# LineSensors.net
KiCad netlist of a schematic drawn in Altium Designer
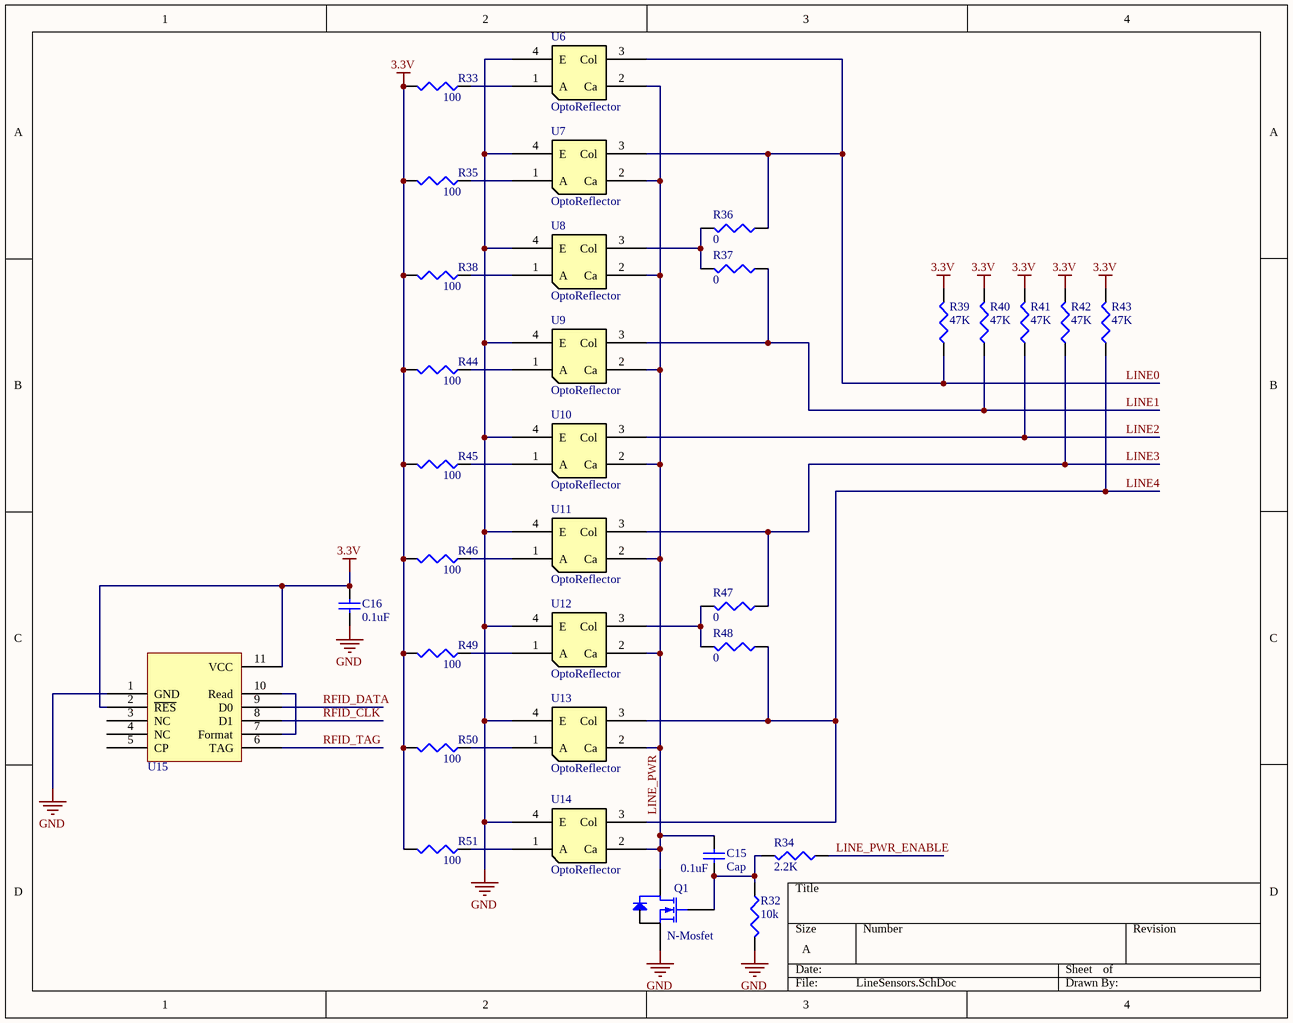
[diagram p0: LineSensors.SchDoc]

(export (version "E")
  (design (tool "Eeschema 10.0.6"))
  (components
    (comp (ref "C15")
      (value "Cap")
      (footprint "CAPC1005L")
      (description "Capacitor")
      (fields (field (name "ALTIUM_VALUE") "0.1uF") (field (name "PUBLISHER") "Altium Limited"))
      (libsource (lib "mrone") (part "Cap"))
    )
    (comp (ref "C16")
      (value "0.1uF")
      (footprint "CAPC1005L")
      (description "Capacitor (Semiconductor SIM Model)")
      (fields (field (name "Comment") "Cap Semi") (field (name "PUBLISHER") "Altium Limited"))
      (libsource (lib "Miscellaneous Devices") (part "Cap Semi"))
    )
    (comp (ref "Q1") (value "N-Mosfet") (footprint "SOT-23") (libsource (lib "mrone") (part "N-Mosfet")))
    (comp (ref "R32")
      (value "10k")
      (footprint "J1-0603")
      (description "Resistor")
      (fields (field (name "Comment") "Res3") (field (name "PUBLISHER") "Altium Limited"))
      (libsource (lib "Miscellaneous Devices") (part "Res3"))
    )
    (comp (ref "R33")
      (value "100")
      (footprint "J1-0603")
      (description "Resistor")
      (fields (field (name "Comment") "Res3") (field (name "PUBLISHER") "Altium Limited"))
      (libsource (lib "Miscellaneous Devices") (part "Res3"))
    )
    (comp (ref "R34")
      (value "2.2K")
      (footprint "J1-0603")
      (description "Resistor")
      (fields (field (name "Comment") "Res3") (field (name "PUBLISHER") "Altium Limited"))
      (libsource (lib "Miscellaneous Devices") (part "Res3"))
    )
    (comp (ref "R35")
      (value "100")
      (footprint "J1-0603")
      (description "Resistor")
      (fields (field (name "Comment") "Res3") (field (name "PUBLISHER") "Altium Limited"))
      (libsource (lib "Miscellaneous Devices") (part "Res3"))
    )
    (comp (ref "R36")
      (value "0")
      (footprint "J1-0603")
      (description "Resistor")
      (fields (field (name "Comment") "Res3") (field (name "PUBLISHER") "Altium Limited"))
      (libsource (lib "Miscellaneous Devices") (part "Res3"))
    )
    (comp (ref "R37")
      (value "0")
      (footprint "J1-0603")
      (description "Resistor")
      (fields (field (name "Comment") "Res3") (field (name "PUBLISHER") "Altium Limited"))
      (libsource (lib "Miscellaneous Devices") (part "Res3"))
    )
    (comp (ref "R38")
      (value "100")
      (footprint "J1-0603")
      (description "Resistor")
      (fields (field (name "Comment") "Res3") (field (name "PUBLISHER") "Altium Limited"))
      (libsource (lib "Miscellaneous Devices") (part "Res3"))
    )
    (comp (ref "R39")
      (value "47K")
      (footprint "J1-0603")
      (description "Resistor")
      (fields (field (name "Comment") "Res3") (field (name "PUBLISHER") "Altium Limited"))
      (libsource (lib "Miscellaneous Devices") (part "Res3"))
    )
    (comp (ref "R40")
      (value "47K")
      (footprint "J1-0603")
      (description "Resistor")
      (fields (field (name "Comment") "Res3") (field (name "PUBLISHER") "Altium Limited"))
      (libsource (lib "Miscellaneous Devices") (part "Res3"))
    )
    (comp (ref "R41")
      (value "47K")
      (footprint "J1-0603")
      (description "Resistor")
      (fields (field (name "Comment") "Res3") (field (name "PUBLISHER") "Altium Limited"))
      (libsource (lib "Miscellaneous Devices") (part "Res3"))
    )
    (comp (ref "R42")
      (value "47K")
      (footprint "J1-0603")
      (description "Resistor")
      (fields (field (name "Comment") "Res3") (field (name "PUBLISHER") "Altium Limited"))
      (libsource (lib "Miscellaneous Devices") (part "Res3"))
    )
    (comp (ref "R43")
      (value "47K")
      (footprint "J1-0603")
      (description "Resistor")
      (fields (field (name "Comment") "Res3") (field (name "PUBLISHER") "Altium Limited"))
      (libsource (lib "Miscellaneous Devices") (part "Res3"))
    )
    (comp (ref "R44")
      (value "100")
      (footprint "J1-0603")
      (description "Resistor")
      (fields (field (name "Comment") "Res3") (field (name "PUBLISHER") "Altium Limited"))
      (libsource (lib "Miscellaneous Devices") (part "Res3"))
    )
    (comp (ref "R45")
      (value "100")
      (footprint "J1-0603")
      (description "Resistor")
      (fields (field (name "Comment") "Res3") (field (name "PUBLISHER") "Altium Limited"))
      (libsource (lib "Miscellaneous Devices") (part "Res3"))
    )
    (comp (ref "R46")
      (value "100")
      (footprint "J1-0603")
      (description "Resistor")
      (fields (field (name "Comment") "Res3") (field (name "PUBLISHER") "Altium Limited"))
      (libsource (lib "Miscellaneous Devices") (part "Res3"))
    )
    (comp (ref "R47")
      (value "0")
      (footprint "J1-0603")
      (description "Resistor")
      (fields (field (name "Comment") "Res3") (field (name "PUBLISHER") "Altium Limited"))
      (libsource (lib "Miscellaneous Devices") (part "Res3"))
    )
    (comp (ref "R48")
      (value "0")
      (footprint "J1-0603")
      (description "Resistor")
      (fields (field (name "Comment") "Res3") (field (name "PUBLISHER") "Altium Limited"))
      (libsource (lib "Miscellaneous Devices") (part "Res3"))
    )
    (comp (ref "R49")
      (value "100")
      (footprint "J1-0603")
      (description "Resistor")
      (fields (field (name "Comment") "Res3") (field (name "PUBLISHER") "Altium Limited"))
      (libsource (lib "Miscellaneous Devices") (part "Res3"))
    )
    (comp (ref "R50")
      (value "100")
      (footprint "J1-0603")
      (description "Resistor")
      (fields (field (name "Comment") "Res3") (field (name "PUBLISHER") "Altium Limited"))
      (libsource (lib "Miscellaneous Devices") (part "Res3"))
    )
    (comp (ref "R51")
      (value "100")
      (footprint "J1-0603")
      (description "Resistor")
      (fields (field (name "Comment") "Res3") (field (name "PUBLISHER") "Altium Limited"))
      (libsource (lib "Miscellaneous Devices") (part "Res3"))
    )
    (comp (ref "U6")
      (value "OptoReflector")
      (footprint "QRE1113")
      (libsource (lib "mrone") (part "QRE1113GR"))
    )
    (comp (ref "U7")
      (value "OptoReflector")
      (footprint "QRE1113")
      (libsource (lib "mrone") (part "QRE1113GR"))
    )
    (comp (ref "U8")
      (value "OptoReflector")
      (footprint "QRE1113")
      (libsource (lib "mrone") (part "QRE1113GR"))
    )
    (comp (ref "U9")
      (value "OptoReflector")
      (footprint "QRE1113")
      (libsource (lib "mrone") (part "QRE1113GR"))
    )
    (comp (ref "U10")
      (value "OptoReflector")
      (footprint "QRE1113")
      (libsource (lib "mrone") (part "QRE1113GR"))
    )
    (comp (ref "U11")
      (value "OptoReflector")
      (footprint "QRE1113")
      (libsource (lib "mrone") (part "QRE1113GR"))
    )
    (comp (ref "U12")
      (value "OptoReflector")
      (footprint "QRE1113")
      (libsource (lib "mrone") (part "QRE1113GR"))
    )
    (comp (ref "U13")
      (value "OptoReflector")
      (footprint "QRE1113")
      (libsource (lib "mrone") (part "QRE1113GR"))
    )
    (comp (ref "U14")
      (value "OptoReflector")
      (footprint "QRE1113")
      (libsource (lib "mrone") (part "QRE1113GR"))
    )
    (comp (ref "U15") (value "ID-12LA") (footprint "ID12-LA") (libsource (lib "mrone") (part "ID-12LA")))
  )
  (nets
    (net (code "1") (name "/LINE0") (class "Default")
      (node (ref "R36") (pin "1") (pinfunction "1_1") (pintype "passive"))
      (node (ref "R39") (pin "1") (pinfunction "1_1") (pintype "passive"))
      (node (ref "U6") (pin "3") (pinfunction "Col_3") (pintype "passive"))
      (node (ref "U7") (pin "3") (pinfunction "Col_3") (pintype "passive"))
    )
    (net (code "2") (name "/LINE1") (class "Default")
      (node (ref "R37") (pin "1") (pinfunction "1_1") (pintype "passive"))
      (node (ref "R40") (pin "1") (pinfunction "1_1") (pintype "passive"))
      (node (ref "U9") (pin "3") (pinfunction "Col_3") (pintype "passive"))
    )
    (net (code "3") (name "/LINE2") (class "Default")
      (node (ref "R41") (pin "1") (pinfunction "1_1") (pintype "passive"))
      (node (ref "U10") (pin "3") (pinfunction "Col_3") (pintype "passive"))
    )
    (net (code "4") (name "/LINE3") (class "Default")
      (node (ref "R42") (pin "1") (pinfunction "1_1") (pintype "passive"))
      (node (ref "R47") (pin "1") (pinfunction "1_1") (pintype "passive"))
      (node (ref "U11") (pin "3") (pinfunction "Col_3") (pintype "passive"))
    )
    (net (code "5") (name "/LINE4") (class "Default")
      (node (ref "R43") (pin "1") (pinfunction "1_1") (pintype "passive"))
      (node (ref "R48") (pin "1") (pinfunction "1_1") (pintype "passive"))
      (node (ref "U13") (pin "3") (pinfunction "Col_3") (pintype "passive"))
      (node (ref "U14") (pin "3") (pinfunction "Col_3") (pintype "passive"))
    )
    (net (code "6") (name "/LINE_PWR") (class "Default")
      (node (ref "C15") (pin "1") (pinfunction "1_1") (pintype "passive"))
      (node (ref "Q1") (pin "3") (pinfunction "D_3") (pintype "passive"))
      (node (ref "U10") (pin "2") (pinfunction "Ca_2") (pintype "passive"))
      (node (ref "U11") (pin "2") (pinfunction "Ca_2") (pintype "passive"))
      (node (ref "U12") (pin "2") (pinfunction "Ca_2") (pintype "passive"))
      (node (ref "U13") (pin "2") (pinfunction "Ca_2") (pintype "passive"))
      (node (ref "U14") (pin "2") (pinfunction "Ca_2") (pintype "passive"))
      (node (ref "U6") (pin "2") (pinfunction "Ca_2") (pintype "passive"))
      (node (ref "U7") (pin "2") (pinfunction "Ca_2") (pintype "passive"))
      (node (ref "U8") (pin "2") (pinfunction "Ca_2") (pintype "passive"))
      (node (ref "U9") (pin "2") (pinfunction "Ca_2") (pintype "passive"))
    )
    (net (code "7") (name "/LINE_PWR_ENABLE") (class "Default")
      (node (ref "R34") (pin "2") (pinfunction "2_2") (pintype "passive"))
    )
    (net (code "8") (name "/RFID_CLK") (class "Default")
      (node (ref "U15") (pin "8") (pinfunction "D1_8") (pintype "power_in"))
    )
    (net (code "9") (name "/RFID_DATA") (class "Default")
      (node (ref "U15") (pin "9") (pinfunction "D0_9") (pintype "power_in"))
    )
    (net (code "10") (name "/RFID_TAG") (class "Default")
      (node (ref "U15") (pin "6") (pinfunction "TAG_6") (pintype "power_in"))
    )
    (net (code "11") (name "3.3V") (class "Default")
      (node (ref "C16") (pin "2") (pinfunction "2_2") (pintype "passive"))
      (node (ref "R33") (pin "2") (pinfunction "2_2") (pintype "passive"))
      (node (ref "R35") (pin "2") (pinfunction "2_2") (pintype "passive"))
      (node (ref "R38") (pin "2") (pinfunction "2_2") (pintype "passive"))
      (node (ref "R39") (pin "2") (pinfunction "2_2") (pintype "passive"))
      (node (ref "R40") (pin "2") (pinfunction "2_2") (pintype "passive"))
      (node (ref "R41") (pin "2") (pinfunction "2_2") (pintype "passive"))
      (node (ref "R42") (pin "2") (pinfunction "2_2") (pintype "passive"))
      (node (ref "R43") (pin "2") (pinfunction "2_2") (pintype "passive"))
      (node (ref "R44") (pin "2") (pinfunction "2_2") (pintype "passive"))
      (node (ref "R45") (pin "2") (pinfunction "2_2") (pintype "passive"))
      (node (ref "R46") (pin "2") (pinfunction "2_2") (pintype "passive"))
      (node (ref "R49") (pin "2") (pinfunction "2_2") (pintype "passive"))
      (node (ref "R50") (pin "2") (pinfunction "2_2") (pintype "passive"))
      (node (ref "R51") (pin "2") (pinfunction "2_2") (pintype "passive"))
      (node (ref "U15") (pin "11") (pinfunction "VCC_11") (pintype "power_in"))
      (node (ref "U15") (pin "2") (pinfunction "RES_2") (pintype "passive"))
    )
    (net (code "12") (name "GND") (class "Default")
      (node (ref "C16") (pin "1") (pinfunction "1_1") (pintype "passive"))
      (node (ref "Q1") (pin "2") (pinfunction "S_2") (pintype "passive"))
      (node (ref "R32") (pin "1") (pinfunction "1_1") (pintype "passive"))
      (node (ref "U10") (pin "4") (pinfunction "E_4") (pintype "passive"))
      (node (ref "U11") (pin "4") (pinfunction "E_4") (pintype "passive"))
      (node (ref "U12") (pin "4") (pinfunction "E_4") (pintype "passive"))
      (node (ref "U13") (pin "4") (pinfunction "E_4") (pintype "passive"))
      (node (ref "U14") (pin "4") (pinfunction "E_4") (pintype "passive"))
      (node (ref "U15") (pin "1") (pinfunction "GND_1") (pintype "passive"))
      (node (ref "U6") (pin "4") (pinfunction "E_4") (pintype "passive"))
      (node (ref "U7") (pin "4") (pinfunction "E_4") (pintype "passive"))
      (node (ref "U8") (pin "4") (pinfunction "E_4") (pintype "passive"))
      (node (ref "U9") (pin "4") (pinfunction "E_4") (pintype "passive"))
    )
    (net (code "13") (name "Net-(Q1-G)") (class "Default")
      (node (ref "C15") (pin "2") (pinfunction "2_2") (pintype "passive"))
      (node (ref "Q1") (pin "1") (pinfunction "G_1") (pintype "passive"))
      (node (ref "R32") (pin "2") (pinfunction "2_2") (pintype "passive"))
      (node (ref "R34") (pin "1") (pinfunction "1_1") (pintype "passive"))
    )
    (net (code "14") (name "Net-(U6-A)") (class "Default")
      (node (ref "R33") (pin "1") (pinfunction "1_1") (pintype "passive"))
      (node (ref "U6") (pin "1") (pinfunction "A_1") (pintype "passive"))
    )
    (net (code "15") (name "Net-(U7-A)") (class "Default")
      (node (ref "R35") (pin "1") (pinfunction "1_1") (pintype "passive"))
      (node (ref "U7") (pin "1") (pinfunction "A_1") (pintype "passive"))
    )
    (net (code "16") (name "Net-(U8-A)") (class "Default")
      (node (ref "R38") (pin "1") (pinfunction "1_1") (pintype "passive"))
      (node (ref "U8") (pin "1") (pinfunction "A_1") (pintype "passive"))
    )
    (net (code "17") (name "Net-(U8-Col)") (class "Default")
      (node (ref "R36") (pin "2") (pinfunction "2_2") (pintype "passive"))
      (node (ref "R37") (pin "2") (pinfunction "2_2") (pintype "passive"))
      (node (ref "U8") (pin "3") (pinfunction "Col_3") (pintype "passive"))
    )
    (net (code "18") (name "Net-(U9-A)") (class "Default")
      (node (ref "R44") (pin "1") (pinfunction "1_1") (pintype "passive"))
      (node (ref "U9") (pin "1") (pinfunction "A_1") (pintype "passive"))
    )
    (net (code "19") (name "Net-(U10-A)") (class "Default")
      (node (ref "R45") (pin "1") (pinfunction "1_1") (pintype "passive"))
      (node (ref "U10") (pin "1") (pinfunction "A_1") (pintype "passive"))
    )
    (net (code "20") (name "Net-(U11-A)") (class "Default")
      (node (ref "R46") (pin "1") (pinfunction "1_1") (pintype "passive"))
      (node (ref "U11") (pin "1") (pinfunction "A_1") (pintype "passive"))
    )
    (net (code "21") (name "Net-(U12-A)") (class "Default")
      (node (ref "R49") (pin "1") (pinfunction "1_1") (pintype "passive"))
      (node (ref "U12") (pin "1") (pinfunction "A_1") (pintype "passive"))
    )
    (net (code "22") (name "Net-(U12-Col)") (class "Default")
      (node (ref "R47") (pin "2") (pinfunction "2_2") (pintype "passive"))
      (node (ref "R48") (pin "2") (pinfunction "2_2") (pintype "passive"))
      (node (ref "U12") (pin "3") (pinfunction "Col_3") (pintype "passive"))
    )
    (net (code "23") (name "Net-(U13-A)") (class "Default")
      (node (ref "R50") (pin "1") (pinfunction "1_1") (pintype "passive"))
      (node (ref "U13") (pin "1") (pinfunction "A_1") (pintype "passive"))
    )
    (net (code "24") (name "Net-(U14-A)") (class "Default")
      (node (ref "R51") (pin "1") (pinfunction "1_1") (pintype "passive"))
      (node (ref "U14") (pin "1") (pinfunction "A_1") (pintype "passive"))
    )
    (net (code "25") (name "Net-(U15-Format)") (class "Default")
      (node (ref "U15") (pin "10") (pinfunction "Read_10") (pintype "power_in"))
      (node (ref "U15") (pin "7") (pinfunction "Format_7") (pintype "passive"))
    )
    (net (code "26") (name "unconnected-(U15-CP-Pad5)") (class "Default")
      (node (ref "U15") (pin "5") (pinfunction "CP_5") (pintype "passive"))
    )
    (net (code "27") (name "unconnected-(U15-NC-Pad3)") (class "Default")
      (node (ref "U15") (pin "3") (pinfunction "NC_3") (pintype "power_in"))
    )
    (net (code "28") (name "unconnected-(U15-NC-Pad4)") (class "Default")
      (node (ref "U15") (pin "4") (pinfunction "NC_4") (pintype "power_in"))
    )
  )
)
